# BandpassedGainAmpThruhole.net
KiCad netlist of a schematic drawn in EAGLE
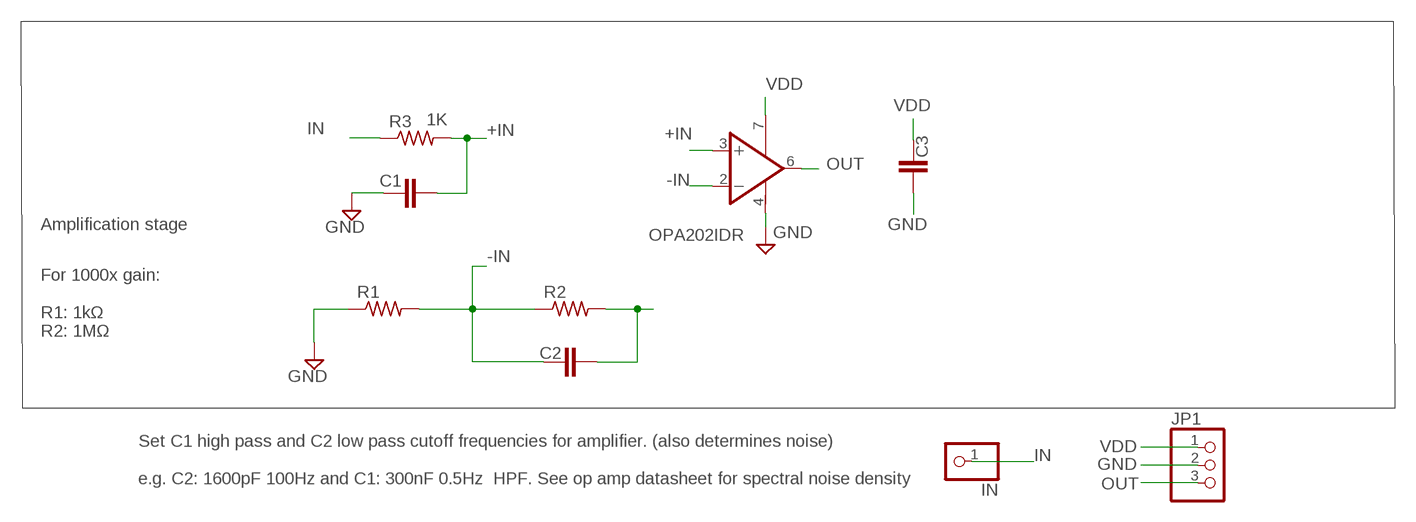
[diagram p0: schematic, sheet 1]

(export (version "E")
  (design (tool "Eeschema 10.0.6"))
  (components
    (comp (ref "C1")
      (value "C2.5/2")
      (footprint "eagle-import:C2.5-2")
      (libsource (lib "eagle-import") (part "C2.5/2"))
    )
    (comp (ref "C2")
      (value "C2.5/2")
      (footprint "eagle-import:C2.5-2")
      (libsource (lib "eagle-import") (part "C2.5/2"))
    )
    (comp (ref "C3")
      (value "C2.5/2")
      (footprint "eagle-import:C2.5-2")
      (libsource (lib "eagle-import") (part "C2.5/2"))
    )
    (comp (ref "IN")
      (value "PINHD-1X1")
      (footprint "eagle-import:1X01")
      (libsource (lib "eagle-import") (part "PINHD-1X1"))
    )
    (comp (ref "JP1")
      (value "PINHD-1X3")
      (footprint "eagle-import:1X03")
      (libsource (lib "eagle-import") (part "PINHD-1X3"))
    )
    (comp (ref "R1")
      (value "R-US_0204/5")
      (footprint "eagle-import:0204_5")
      (libsource (lib "eagle-import") (part "R-US_0204/5"))
    )
    (comp (ref "R2")
      (value "R-US_0204/5")
      (footprint "eagle-import:0204_5")
      (libsource (lib "eagle-import") (part "R-US_0204/5"))
    )
    (comp (ref "R3")
      (value "1K")
      (footprint "eagle-import:0204_5")
      (libsource (lib "eagle-import") (part "R-US_0204/5"))
    )
    (comp (ref "U1")
      (value "OPA202IDR")
      (footprint "eagle-import:SOIC127P600X175-8N")
      (fields (field (name "MF") "Texas Instruments"))
      (libsource (lib "eagle-import") (part "OPA202IDR"))
    )
  )
  (nets
    (net (code "1") (name "/+IN") (class "Default")
      (node (ref "C1") (pin "2") (pinfunction "2_2") (pintype "passive"))
      (node (ref "R3") (pin "2") (pinfunction "2_2") (pintype "passive"))
      (node (ref "U1") (pin "3") (pinfunction "+IN_3") (pintype "input"))
    )
    (net (code "2") (name "/-IN") (class "Default")
      (node (ref "C2") (pin "1") (pinfunction "1_1") (pintype "passive"))
      (node (ref "R1") (pin "2") (pinfunction "2_2") (pintype "passive"))
      (node (ref "R2") (pin "1") (pinfunction "1_1") (pintype "passive"))
      (node (ref "U1") (pin "2") (pinfunction "-IN_2") (pintype "input"))
    )
    (net (code "3") (name "/IN") (class "Default")
      (node (ref "IN") (pin "1") (pinfunction "1_1") (pintype "passive"))
      (node (ref "R3") (pin "1") (pinfunction "1_1") (pintype "passive"))
    )
    (net (code "4") (name "/OUT") (class "Default")
      (node (ref "JP1") (pin "3") (pinfunction "3_3") (pintype "passive"))
      (node (ref "U1") (pin "6") (pinfunction "OUT_6") (pintype "output"))
    )
    (net (code "5") (name "/VDD") (class "Default")
      (node (ref "C3") (pin "1") (pinfunction "1_1") (pintype "passive"))
      (node (ref "JP1") (pin "1") (pinfunction "1_1") (pintype "passive"))
      (node (ref "U1") (pin "7") (pinfunction "V+_7") (pintype "power_in"))
    )
    (net (code "6") (name "GND") (class "Default")
      (node (ref "C1") (pin "1") (pinfunction "1_1") (pintype "passive"))
      (node (ref "C3") (pin "2") (pinfunction "2_2") (pintype "passive"))
      (node (ref "JP1") (pin "2") (pinfunction "2_2") (pintype "passive"))
      (node (ref "R1") (pin "1") (pinfunction "1_1") (pintype "passive"))
      (node (ref "U1") (pin "4") (pinfunction "V-_4") (pintype "power_in"))
    )
    (net (code "7") (name "Net-(C2-Pad2)") (class "Default")
      (node (ref "C2") (pin "2") (pinfunction "2_2") (pintype "passive"))
      (node (ref "R2") (pin "2") (pinfunction "2_2") (pintype "passive"))
    )
  )
)
